# Grove_-_IMU_9DOF_v2_0.net
KiCad netlist of a schematic drawn in EAGLE
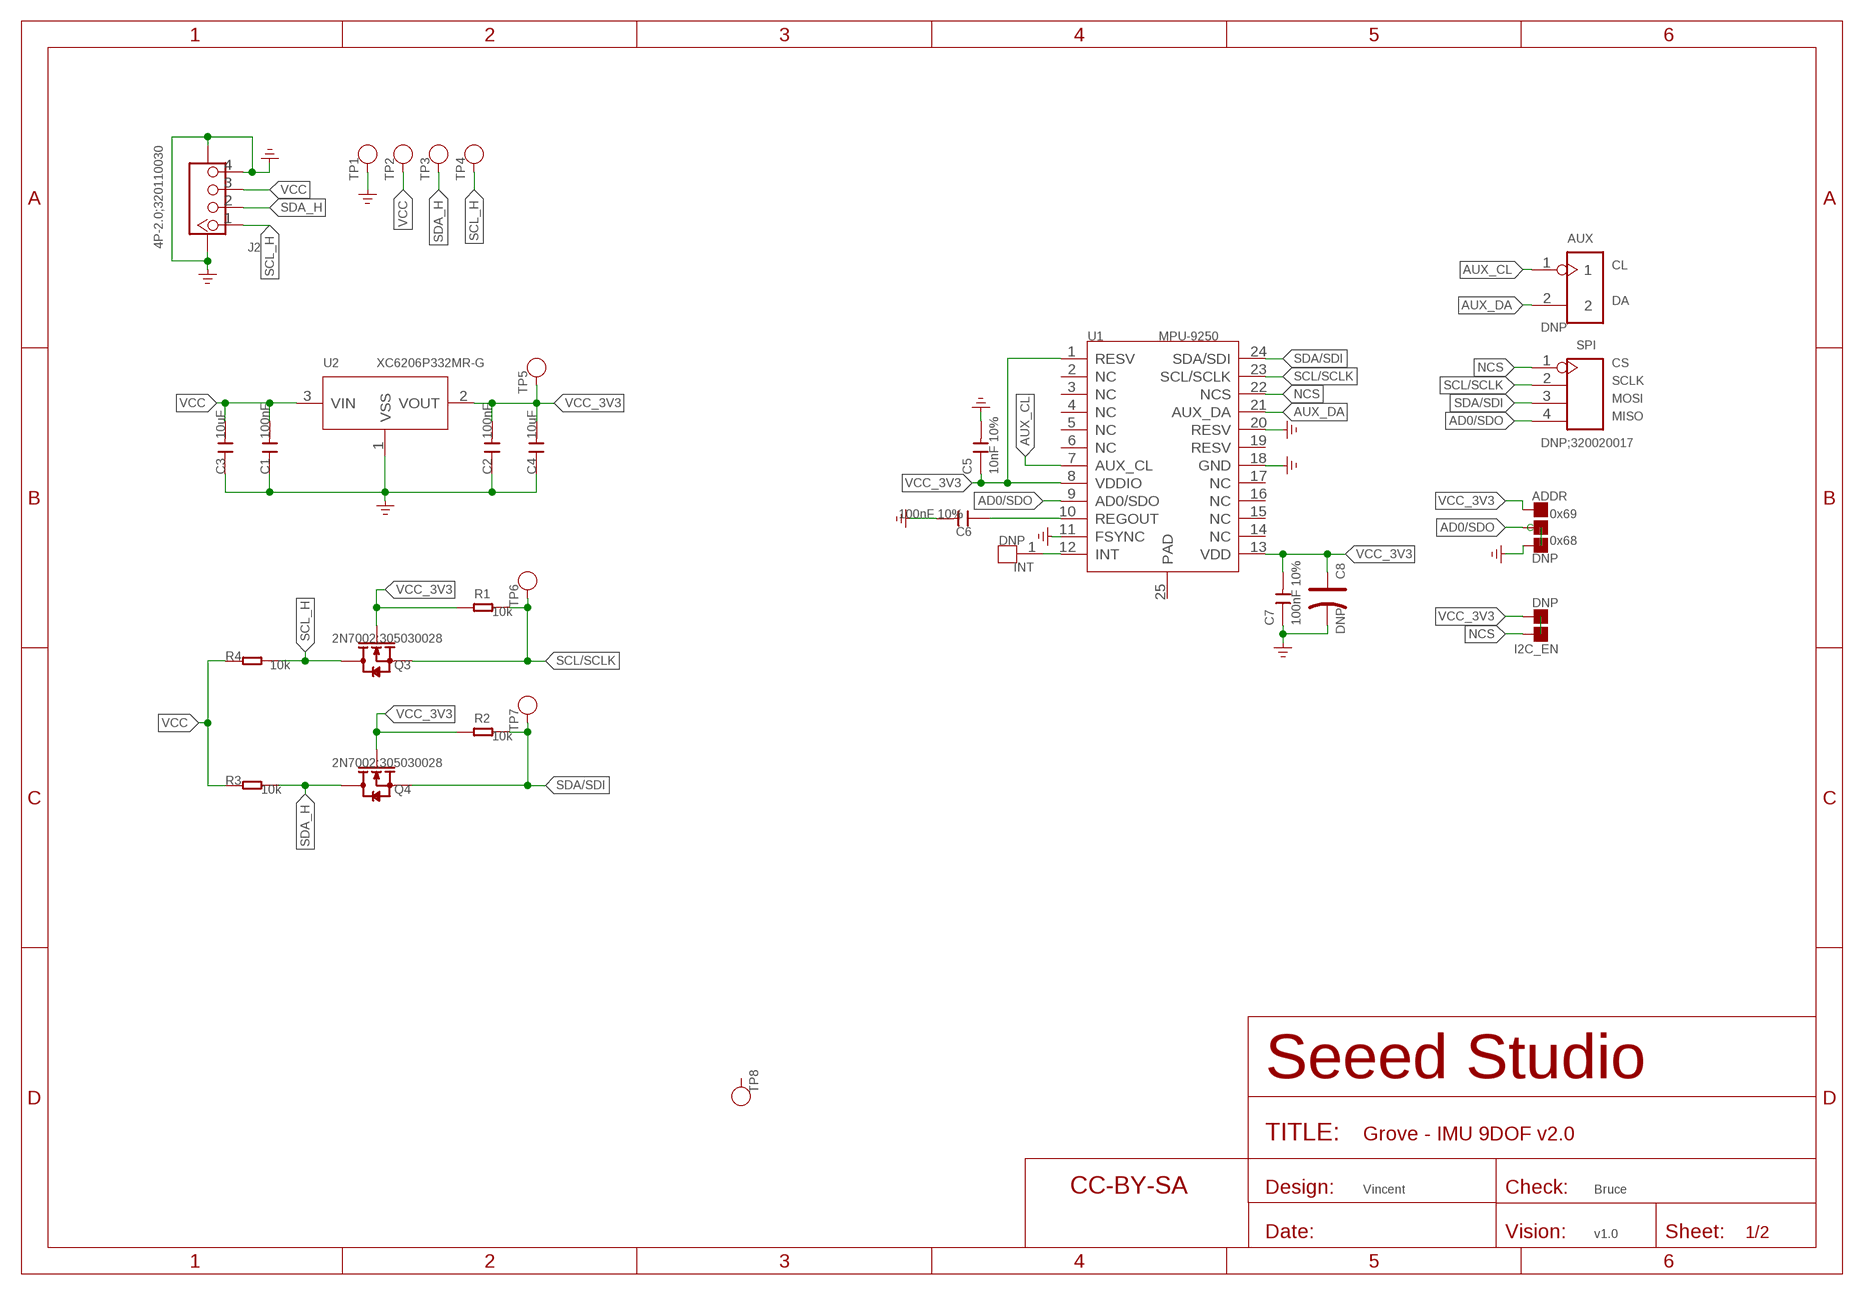
[diagram p0: schematic, sheet 1]

(export (version "E")
  (design (tool "Eeschema 10.0.6"))
  (components
    (comp (ref "ADDR")
      (value "DNP")
      (footprint "eagle-import:3P-SMD-L4.1_W1.5MM")
      (libsource (lib "eagle-import") (part "PAD-JUMPER-3P-4040"))
    )
    (comp (ref "AUX")
      (value "DNP")
      (footprint "eagle-import:2P-2.54-65_35MIL")
      (libsource (lib "eagle-import") (part "HEADER-2P-65/35MIL"))
    )
    (comp (ref "C1")
      (value "100nF")
      (footprint "eagle-import:C0603")
      (libsource (lib "eagle-import") (part "CAP-0603"))
    )
    (comp (ref "C2")
      (value "100nF")
      (footprint "eagle-import:C0603")
      (libsource (lib "eagle-import") (part "CAP-0603"))
    )
    (comp (ref "C3")
      (value "10uF")
      (footprint "eagle-import:C0805")
      (libsource (lib "eagle-import") (part "CAP-0805"))
    )
    (comp (ref "C4")
      (value "10uF")
      (footprint "eagle-import:C0805")
      (libsource (lib "eagle-import") (part "CAP-0805"))
    )
    (comp (ref "C5")
      (value "10nF 10%")
      (footprint "eagle-import:C0603")
      (libsource (lib "eagle-import") (part "CAP-0603"))
    )
    (comp (ref "C6")
      (value "100nF 10%")
      (footprint "eagle-import:C0603")
      (libsource (lib "eagle-import") (part "CAP-0603"))
    )
    (comp (ref "C7")
      (value "100nF 10%")
      (footprint "eagle-import:C0603")
      (libsource (lib "eagle-import") (part "CAP-0603"))
    )
    (comp (ref "C8")
      (value "DNP")
      (footprint "eagle-import:AVX-A")
      (libsource (lib "eagle-import") (part "CAP-POLAR-AVX-A"))
    )
    (comp (ref "I2C_EN")
      (value "DNP")
      (footprint "eagle-import:2P-SMD-L1.78_W1.27MM")
      (libsource (lib "eagle-import") (part "PAD-JUMPER-2P"))
    )
    (comp (ref "INT")
      (value "DNP")
      (footprint "eagle-import:1P-65_35MIL")
      (libsource (lib "eagle-import") (part "HEADER-1P-35"))
    )
    (comp (ref "J2")
      (value "4P-2.0;320110030")
      (footprint "eagle-import:4P-SMD-2.0")
      (libsource (lib "eagle-import") (part "GROVE-CONNECTOR-SMD'DD'"))
    )
    (comp (ref "Q3")
      (value "2N7002;305030028")
      (footprint "eagle-import:SOT-23")
      (libsource (lib "eagle-import") (part "MOSFET-N'SOT23'"))
    )
    (comp (ref "Q4")
      (value "2N7002;305030028")
      (footprint "eagle-import:SOT-23")
      (libsource (lib "eagle-import") (part "MOSFET-N'SOT23'"))
    )
    (comp (ref "R1")
      (value "10k")
      (footprint "eagle-import:R0603")
      (libsource (lib "eagle-import") (part "RES-0603"))
    )
    (comp (ref "R2")
      (value "10k")
      (footprint "eagle-import:R0603")
      (libsource (lib "eagle-import") (part "RES-0603"))
    )
    (comp (ref "R3")
      (value "10k")
      (footprint "eagle-import:R0603")
      (libsource (lib "eagle-import") (part "RES-0603"))
    )
    (comp (ref "R4")
      (value "10k")
      (footprint "eagle-import:R0603")
      (libsource (lib "eagle-import") (part "RES-0603"))
    )
    (comp (ref "SPI")
      (value "DNP;320020017")
      (footprint "eagle-import:4P-2.54-65_35MIL")
      (libsource (lib "eagle-import") (part "HEADER-4P-65/35MIL"))
    )
    (comp (ref "TP1")
      (value "DNP")
      (footprint "eagle-import:TP-D45MIL")
      (libsource (lib "eagle-import") (part "PAD-TEST-POINT'4545'"))
    )
    (comp (ref "TP2")
      (value "DNP")
      (footprint "eagle-import:TP-D45MIL")
      (libsource (lib "eagle-import") (part "PAD-TEST-POINT'4545'"))
    )
    (comp (ref "TP3")
      (value "DNP")
      (footprint "eagle-import:TP-D45MIL")
      (libsource (lib "eagle-import") (part "PAD-TEST-POINT'4545'"))
    )
    (comp (ref "TP4")
      (value "DNP")
      (footprint "eagle-import:TP-D45MIL")
      (libsource (lib "eagle-import") (part "PAD-TEST-POINT'4545'"))
    )
    (comp (ref "TP5")
      (value "DNP")
      (footprint "eagle-import:TP-D45MIL")
      (libsource (lib "eagle-import") (part "PAD-TEST-POINT'4545'"))
    )
    (comp (ref "TP6")
      (value "DNP")
      (footprint "eagle-import:TP-D45MIL")
      (libsource (lib "eagle-import") (part "PAD-TEST-POINT'4545'"))
    )
    (comp (ref "TP7")
      (value "DNP")
      (footprint "eagle-import:TP-D45MIL")
      (libsource (lib "eagle-import") (part "PAD-TEST-POINT'4545'"))
    )
    (comp (ref "TP8")
      (value "DNP")
      (footprint "eagle-import:TP-D45MIL")
      (libsource (lib "eagle-import") (part "PAD-TEST-POINT'4545'"))
    )
    (comp (ref "U$1")
      (value "SEEEDSTUDIO-OPEN-SCH-FRAME")
      (footprint "eagle-import:SEEEDSTUDIO-PCB-FRAME")
      (libsource (lib "eagle-import") (part "SEEEDSTUDIO-OPEN-SCH-FRAME"))
    )
    (comp (ref "U1")
      (value "MPU-9250")
      (footprint "eagle-import:LEAD-QFN24")
      (libsource (lib "eagle-import") (part "MPU-9250"))
    )
    (comp (ref "U2")
      (value "XC6206P332MR-G")
      (footprint "eagle-import:SOT-23")
      (libsource (lib "eagle-import") (part "PMIC-XC6206PMR"))
    )
  )
  (nets
    (net (code "1") (name "AD0{slash}SDO") (class "Default")
      (node (ref "ADDR") (pin "MM") (pinfunction "C_MM") (pintype "bidirectional"))
      (node (ref "SPI") (pin "4") (pinfunction "P$4_4") (pintype "bidirectional"))
      (node (ref "U1") (pin "9") (pinfunction "AD0/SDO_9") (pintype "bidirectional"))
    )
    (net (code "2") (name "AUX_CL") (class "Default")
      (node (ref "AUX") (pin "1") (pinfunction "1_1") (pintype "bidirectional"))
      (node (ref "U1") (pin "7") (pinfunction "AUX_CL_7") (pintype "bidirectional"))
    )
    (net (code "3") (name "AUX_DA") (class "Default")
      (node (ref "AUX") (pin "2") (pinfunction "2_2") (pintype "bidirectional"))
      (node (ref "U1") (pin "21") (pinfunction "AUX_DA_21") (pintype "bidirectional"))
    )
    (net (code "4") (name "GND") (class "Default")
      (node (ref "ADDR") (pin "11") (pinfunction "R_11") (pintype "bidirectional"))
      (node (ref "C1") (pin "1") (pinfunction "1_1") (pintype "passive"))
      (node (ref "C2") (pin "1") (pinfunction "1_1") (pintype "passive"))
      (node (ref "C3") (pin "1") (pinfunction "1_1") (pintype "passive"))
      (node (ref "C4") (pin "1") (pinfunction "1_1") (pintype "passive"))
      (node (ref "C5") (pin "2") (pinfunction "2_2") (pintype "passive"))
      (node (ref "C6") (pin "2") (pinfunction "2_2") (pintype "passive"))
      (node (ref "C7") (pin "1") (pinfunction "1_1") (pintype "passive"))
      (node (ref "C8") (pin "-") (pinfunction "-_-") (pintype "passive"))
      (node (ref "J2") (pin "4") (pinfunction "4_4") (pintype "bidirectional"))
      (node (ref "J2") (pin "SS1") (pinfunction "SS1_SS1") (pintype "bidirectional"))
      (node (ref "J2") (pin "SS2") (pinfunction "SS2_SS2") (pintype "bidirectional"))
      (node (ref "TP1") (pin "T") (pinfunction "T_T") (pintype "bidirectional"))
      (node (ref "U1") (pin "11") (pinfunction "FSYNC_11") (pintype "bidirectional"))
      (node (ref "U1") (pin "18") (pinfunction "GND_18") (pintype "bidirectional"))
      (node (ref "U1") (pin "20") (pinfunction "RESV_20") (pintype "bidirectional"))
      (node (ref "U2") (pin "1") (pinfunction "VSS_1") (pintype "power_in"))
    )
    (net (code "5") (name "NCS") (class "Default")
      (node (ref "I2C_EN") (pin "2") (pinfunction "2_2") (pintype "bidirectional"))
      (node (ref "SPI") (pin "1") (pinfunction "P$1_1") (pintype "bidirectional"))
      (node (ref "U1") (pin "22") (pinfunction "NCS_22") (pintype "bidirectional"))
    )
    (net (code "6") (name "Net-(U1-INT)") (class "Default")
      (node (ref "INT") (pin "1") (pinfunction "1_1") (pintype "bidirectional"))
      (node (ref "U1") (pin "12") (pinfunction "INT_12") (pintype "bidirectional"))
    )
    (net (code "7") (name "Net-(U1-REGOUT)") (class "Default")
      (node (ref "C6") (pin "1") (pinfunction "1_1") (pintype "passive"))
      (node (ref "U1") (pin "10") (pinfunction "REGOUT_10") (pintype "bidirectional"))
    )
    (net (code "8") (name "SCL_H") (class "Default")
      (node (ref "J2") (pin "1") (pinfunction "1_1") (pintype "bidirectional"))
      (node (ref "Q3") (pin "3") (pinfunction "D_3") (pintype "passive"))
      (node (ref "R4") (pin "2") (pinfunction "2_2") (pintype "passive"))
      (node (ref "TP4") (pin "T") (pinfunction "T_T") (pintype "bidirectional"))
    )
    (net (code "9") (name "SCL{slash}SCLK") (class "Default")
      (node (ref "Q3") (pin "2") (pinfunction "S_2") (pintype "passive"))
      (node (ref "R1") (pin "2") (pinfunction "2_2") (pintype "passive"))
      (node (ref "SPI") (pin "2") (pinfunction "P$2_2") (pintype "bidirectional"))
      (node (ref "TP6") (pin "T") (pinfunction "T_T") (pintype "bidirectional"))
      (node (ref "U1") (pin "23") (pinfunction "SCL/SCLK_23") (pintype "bidirectional"))
    )
    (net (code "10") (name "SDA_H") (class "Default")
      (node (ref "J2") (pin "2") (pinfunction "2_2") (pintype "bidirectional"))
      (node (ref "Q4") (pin "3") (pinfunction "D_3") (pintype "passive"))
      (node (ref "R3") (pin "2") (pinfunction "2_2") (pintype "passive"))
      (node (ref "TP3") (pin "T") (pinfunction "T_T") (pintype "bidirectional"))
    )
    (net (code "11") (name "SDA{slash}SDI") (class "Default")
      (node (ref "Q4") (pin "2") (pinfunction "S_2") (pintype "passive"))
      (node (ref "R2") (pin "2") (pinfunction "2_2") (pintype "passive"))
      (node (ref "SPI") (pin "3") (pinfunction "P$3_3") (pintype "bidirectional"))
      (node (ref "TP7") (pin "T") (pinfunction "T_T") (pintype "bidirectional"))
      (node (ref "U1") (pin "24") (pinfunction "SDA/SDI_24") (pintype "bidirectional"))
    )
    (net (code "12") (name "VCC") (class "Default")
      (node (ref "C1") (pin "2") (pinfunction "2_2") (pintype "passive"))
      (node (ref "C3") (pin "2") (pinfunction "2_2") (pintype "passive"))
      (node (ref "J2") (pin "3") (pinfunction "3_3") (pintype "bidirectional"))
      (node (ref "R3") (pin "1") (pinfunction "1_1") (pintype "passive"))
      (node (ref "R4") (pin "1") (pinfunction "1_1") (pintype "passive"))
      (node (ref "TP2") (pin "T") (pinfunction "T_T") (pintype "bidirectional"))
      (node (ref "U2") (pin "3") (pinfunction "VIN_3") (pintype "input"))
    )
    (net (code "13") (name "VCC_3V3") (class "Default")
      (node (ref "ADDR") (pin "00") (pinfunction "L_00") (pintype "bidirectional"))
      (node (ref "C2") (pin "2") (pinfunction "2_2") (pintype "passive"))
      (node (ref "C4") (pin "2") (pinfunction "2_2") (pintype "passive"))
      (node (ref "C5") (pin "1") (pinfunction "1_1") (pintype "passive"))
      (node (ref "C7") (pin "2") (pinfunction "2_2") (pintype "passive"))
      (node (ref "C8") (pin "+") (pinfunction "+_+") (pintype "passive"))
      (node (ref "I2C_EN") (pin "1") (pinfunction "1_1") (pintype "bidirectional"))
      (node (ref "Q3") (pin "1") (pinfunction "G_1") (pintype "passive"))
      (node (ref "Q4") (pin "1") (pinfunction "G_1") (pintype "passive"))
      (node (ref "R1") (pin "1") (pinfunction "1_1") (pintype "passive"))
      (node (ref "R2") (pin "1") (pinfunction "1_1") (pintype "passive"))
      (node (ref "TP5") (pin "T") (pinfunction "T_T") (pintype "bidirectional"))
      (node (ref "U1") (pin "1") (pinfunction "RESV_1") (pintype "bidirectional"))
      (node (ref "U1") (pin "13") (pinfunction "VDD_13") (pintype "bidirectional"))
      (node (ref "U1") (pin "8") (pinfunction "VDDIO_8") (pintype "bidirectional"))
      (node (ref "U2") (pin "2") (pinfunction "VOUT_2") (pintype "output"))
    )
    (net (code "14") (name "unconnected-(TP8-PadT)") (class "Default")
      (node (ref "TP8") (pin "T") (pinfunction "T_T") (pintype "bidirectional"))
    )
    (net (code "15") (name "unconnected-(U1-NC-Pad2)") (class "Default")
      (node (ref "U1") (pin "2") (pinfunction "NC_2") (pintype "bidirectional"))
    )
    (net (code "16") (name "unconnected-(U1-NC-Pad3)") (class "Default")
      (node (ref "U1") (pin "3") (pinfunction "NC_3") (pintype "bidirectional"))
    )
    (net (code "17") (name "unconnected-(U1-NC-Pad4)") (class "Default")
      (node (ref "U1") (pin "4") (pinfunction "NC_4") (pintype "bidirectional"))
    )
    (net (code "18") (name "unconnected-(U1-NC-Pad5)") (class "Default")
      (node (ref "U1") (pin "5") (pinfunction "NC_5") (pintype "bidirectional"))
    )
    (net (code "19") (name "unconnected-(U1-NC-Pad6)") (class "Default")
      (node (ref "U1") (pin "6") (pinfunction "NC_6") (pintype "bidirectional"))
    )
    (net (code "20") (name "unconnected-(U1-NC-Pad14)") (class "Default")
      (node (ref "U1") (pin "14") (pinfunction "NC_14") (pintype "bidirectional"))
    )
    (net (code "21") (name "unconnected-(U1-NC-Pad15)") (class "Default")
      (node (ref "U1") (pin "15") (pinfunction "NC_15") (pintype "bidirectional"))
    )
    (net (code "22") (name "unconnected-(U1-NC-Pad16)") (class "Default")
      (node (ref "U1") (pin "16") (pinfunction "NC_16") (pintype "bidirectional"))
    )
    (net (code "23") (name "unconnected-(U1-NC-Pad17)") (class "Default")
      (node (ref "U1") (pin "17") (pinfunction "NC_17") (pintype "bidirectional"))
    )
    (net (code "24") (name "unconnected-(U1-PAD-Pad25)") (class "Default")
      (node (ref "U1") (pin "25") (pinfunction "PAD_25") (pintype "bidirectional"))
    )
    (net (code "25") (name "unconnected-(U1-RESV-Pad19)") (class "Default")
      (node (ref "U1") (pin "19") (pinfunction "RESV_19") (pintype "bidirectional"))
    )
  )
)
